# TT_PulseGen_V1_1.net
KiCad netlist of a schematic drawn in EAGLE
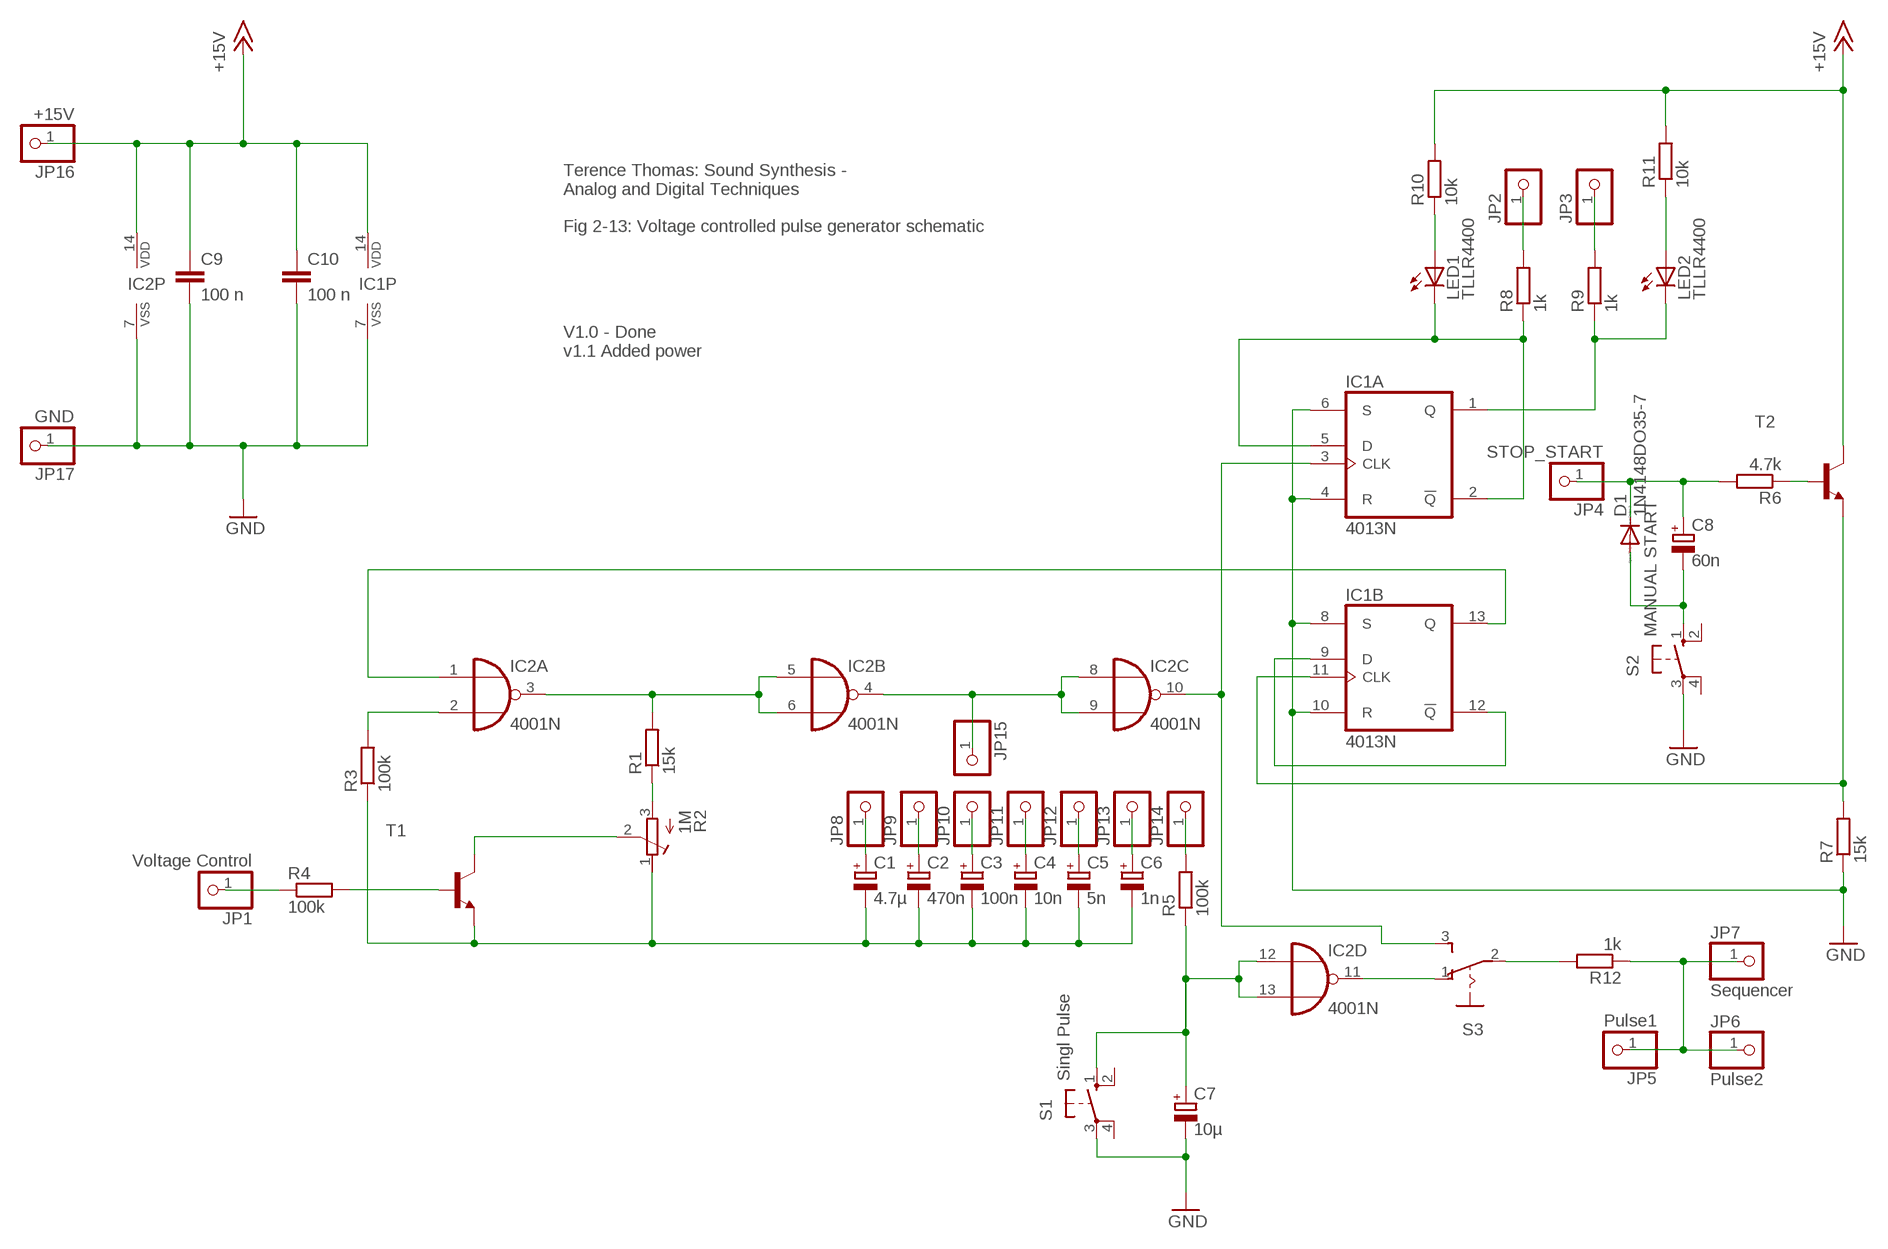
[diagram p0: schematic, sheet 1]

(export (version "E")
  (design (tool "Eeschema 10.0.6"))
  (components
    (comp (ref "C1")
      (value "4.7µ")
      (footprint "eagle-import:E2,5-5")
      (libsource (lib "eagle-import") (part "CPOL-EUE2.5-5"))
    )
    (comp (ref "C2")
      (value "470n")
      (footprint "eagle-import:E2,5-5")
      (libsource (lib "eagle-import") (part "CPOL-EUE2.5-5"))
    )
    (comp (ref "C3")
      (value "100n")
      (footprint "eagle-import:E2,5-5")
      (libsource (lib "eagle-import") (part "CPOL-EUE2.5-5"))
    )
    (comp (ref "C4")
      (value "10n")
      (footprint "eagle-import:E2,5-5")
      (libsource (lib "eagle-import") (part "CPOL-EUE2.5-5"))
    )
    (comp (ref "C5")
      (value "5n")
      (footprint "eagle-import:E2,5-5")
      (libsource (lib "eagle-import") (part "CPOL-EUE2.5-5"))
    )
    (comp (ref "C6")
      (value "1n")
      (footprint "eagle-import:E2,5-5")
      (libsource (lib "eagle-import") (part "CPOL-EUE2.5-5"))
    )
    (comp (ref "C7")
      (value "10µ")
      (footprint "eagle-import:E2,5-5")
      (libsource (lib "eagle-import") (part "CPOL-EUE2.5-5"))
    )
    (comp (ref "C8")
      (value "60n")
      (footprint "eagle-import:E2,5-5")
      (libsource (lib "eagle-import") (part "CPOL-EUE2.5-5"))
    )
    (comp (ref "C9")
      (value "100 n")
      (footprint "eagle-import:C025-030X050")
      (libsource (lib "eagle-import") (part "C-EU025-030X050"))
    )
    (comp (ref "C10")
      (value "100 n")
      (footprint "eagle-import:C025-030X050")
      (libsource (lib "eagle-import") (part "C-EU025-030X050"))
    )
    (comp (ref "D1")
      (value "1N4148DO35-7")
      (footprint "eagle-import:DO35-7")
      (libsource (lib "eagle-import") (part "1N4148DO35-7"))
    )
    (comp (ref "IC1")
      (value "4013N")
      (footprint "eagle-import:DIL14")
      (libsource (lib "eagle-import") (part "4013N"))
    )
    (comp (ref "IC2")
      (value "4001N")
      (footprint "eagle-import:DIL14")
      (libsource (lib "eagle-import") (part "4001N"))
    )
    (comp (ref "JP1")
      (value "Voltage Control")
      (footprint "eagle-import:1X01")
      (libsource (lib "eagle-import") (part "PINHD-1X1"))
    )
    (comp (ref "JP2")
      (value "PINHD-1X1")
      (footprint "eagle-import:1X01")
      (libsource (lib "eagle-import") (part "PINHD-1X1"))
    )
    (comp (ref "JP3")
      (value "PINHD-1X1")
      (footprint "eagle-import:1X01")
      (libsource (lib "eagle-import") (part "PINHD-1X1"))
    )
    (comp (ref "JP4")
      (value "STOP_START")
      (footprint "eagle-import:1X01")
      (libsource (lib "eagle-import") (part "PINHD-1X1"))
    )
    (comp (ref "JP5")
      (value "Pulse1")
      (footprint "eagle-import:1X01")
      (libsource (lib "eagle-import") (part "PINHD-1X1"))
    )
    (comp (ref "JP6")
      (value "Pulse2")
      (footprint "eagle-import:1X01")
      (libsource (lib "eagle-import") (part "PINHD-1X1"))
    )
    (comp (ref "JP7")
      (value "Sequencer")
      (footprint "eagle-import:1X01")
      (libsource (lib "eagle-import") (part "PINHD-1X1"))
    )
    (comp (ref "JP8")
      (value "PINHD-1X1")
      (footprint "eagle-import:1X01")
      (libsource (lib "eagle-import") (part "PINHD-1X1"))
    )
    (comp (ref "JP9")
      (value "PINHD-1X1")
      (footprint "eagle-import:1X01")
      (libsource (lib "eagle-import") (part "PINHD-1X1"))
    )
    (comp (ref "JP10")
      (value "PINHD-1X1")
      (footprint "eagle-import:1X01")
      (libsource (lib "eagle-import") (part "PINHD-1X1"))
    )
    (comp (ref "JP11")
      (value "PINHD-1X1")
      (footprint "eagle-import:1X01")
      (libsource (lib "eagle-import") (part "PINHD-1X1"))
    )
    (comp (ref "JP12")
      (value "PINHD-1X1")
      (footprint "eagle-import:1X01")
      (libsource (lib "eagle-import") (part "PINHD-1X1"))
    )
    (comp (ref "JP13")
      (value "PINHD-1X1")
      (footprint "eagle-import:1X01")
      (libsource (lib "eagle-import") (part "PINHD-1X1"))
    )
    (comp (ref "JP14")
      (value "PINHD-1X1")
      (footprint "eagle-import:1X01")
      (libsource (lib "eagle-import") (part "PINHD-1X1"))
    )
    (comp (ref "JP15")
      (value "PINHD-1X1")
      (footprint "eagle-import:1X01")
      (libsource (lib "eagle-import") (part "PINHD-1X1"))
    )
    (comp (ref "JP16")
      (value "+15V")
      (footprint "eagle-import:1X01")
      (libsource (lib "eagle-import") (part "PINHD-1X1"))
    )
    (comp (ref "JP17")
      (value "GND")
      (footprint "eagle-import:1X01")
      (libsource (lib "eagle-import") (part "PINHD-1X1"))
    )
    (comp (ref "LED1")
      (value "TLLR4400")
      (footprint "eagle-import:LED3MM")
      (fields (field (name "MF") "VISHAY SEMICONDUCTOR"))
      (libsource (lib "eagle-import") (part "TLLR4400"))
    )
    (comp (ref "LED2")
      (value "TLLR4400")
      (footprint "eagle-import:LED3MM")
      (fields (field (name "MF") "VISHAY SEMICONDUCTOR"))
      (libsource (lib "eagle-import") (part "TLLR4400"))
    )
    (comp (ref "R1")
      (value "15k")
      (footprint "eagle-import:0204_7")
      (libsource (lib "eagle-import") (part "R-EU_0204/7"))
    )
    (comp (ref "R2")
      (value "1M")
      (footprint "eagle-import:RTRIMT93YA")
      (libsource (lib "eagle-import") (part "R-TRIMMT93YA"))
    )
    (comp (ref "R3")
      (value "100k")
      (footprint "eagle-import:0204_7")
      (libsource (lib "eagle-import") (part "R-EU_0204/7"))
    )
    (comp (ref "R4")
      (value "100k")
      (footprint "eagle-import:0204_7")
      (libsource (lib "eagle-import") (part "R-EU_0204/7"))
    )
    (comp (ref "R5")
      (value "100k")
      (footprint "eagle-import:0204_7")
      (libsource (lib "eagle-import") (part "R-EU_0204/7"))
    )
    (comp (ref "R6")
      (value "4.7k")
      (footprint "eagle-import:0204_7")
      (libsource (lib "eagle-import") (part "R-EU_0204/7"))
    )
    (comp (ref "R7")
      (value "15k")
      (footprint "eagle-import:0204_7")
      (libsource (lib "eagle-import") (part "R-EU_0204/7"))
    )
    (comp (ref "R8")
      (value "1k")
      (footprint "eagle-import:0204_7")
      (libsource (lib "eagle-import") (part "R-EU_0204/7"))
    )
    (comp (ref "R9")
      (value "1k")
      (footprint "eagle-import:0204_7")
      (libsource (lib "eagle-import") (part "R-EU_0204/7"))
    )
    (comp (ref "R10")
      (value "10k")
      (footprint "eagle-import:0204_7")
      (libsource (lib "eagle-import") (part "R-EU_0204/7"))
    )
    (comp (ref "R11")
      (value "10k")
      (footprint "eagle-import:0204_7")
      (libsource (lib "eagle-import") (part "R-EU_0204/7"))
    )
    (comp (ref "R12")
      (value "1k")
      (footprint "eagle-import:0204_7")
      (libsource (lib "eagle-import") (part "R-EU_0204/7"))
    )
    (comp (ref "S1")
      (value "Singl Pulse")
      (footprint "eagle-import:B3F-10XX")
      (fields (field (name "MPN") "B3F-1000"))
      (libsource (lib "eagle-import") (part "10-XX"))
    )
    (comp (ref "S2")
      (value "MANUAL START")
      (footprint "eagle-import:B3F-10XX")
      (fields (field (name "MPN") "B3F-1000"))
      (libsource (lib "eagle-import") (part "10-XX"))
    )
    (comp (ref "S3")
      (value "M251")
      (footprint "eagle-import:M251")
      (libsource (lib "eagle-import") (part "M251"))
    )
    (comp (ref "T1")
      (value "-NPN-TO92-EBC")
      (footprint "eagle-import:TO92-EBC")
      (libsource (lib "eagle-import") (part "-NPN-TO92-EBC"))
    )
    (comp (ref "T2")
      (value "-NPN-TO92-EBC")
      (footprint "eagle-import:TO92-EBC")
      (libsource (lib "eagle-import") (part "-NPN-TO92-EBC"))
    )
  )
  (nets
    (net (code "1") (name "+15V") (class "Default")
      (node (ref "C10") (pin "1") (pinfunction "1_1") (pintype "passive"))
      (node (ref "C9") (pin "1") (pinfunction "1_1") (pintype "passive"))
      (node (ref "IC1") (pin "14") (pinfunction "VDD_14") (pintype "power_in"))
      (node (ref "IC2") (pin "14") (pinfunction "VDD_14") (pintype "power_in"))
      (node (ref "JP16") (pin "1") (pinfunction "1_1") (pintype "passive"))
      (node (ref "R10") (pin "2") (pinfunction "2_2") (pintype "passive"))
      (node (ref "R11") (pin "2") (pinfunction "2_2") (pintype "passive"))
      (node (ref "T2") (pin "C") (pinfunction "C_C") (pintype "passive"))
    )
    (net (code "2") (name "GND") (class "Default")
      (node (ref "C10") (pin "2") (pinfunction "2_2") (pintype "passive"))
      (node (ref "C7") (pin "-") (pinfunction "-_-") (pintype "passive"))
      (node (ref "C9") (pin "2") (pinfunction "2_2") (pintype "passive"))
      (node (ref "IC1") (pin "10") (pinfunction "R_10") (pintype "input"))
      (node (ref "IC1") (pin "4") (pinfunction "R_4") (pintype "input"))
      (node (ref "IC1") (pin "6") (pinfunction "S_6") (pintype "input"))
      (node (ref "IC1") (pin "7") (pinfunction "VSS_7") (pintype "power_in"))
      (node (ref "IC1") (pin "8") (pinfunction "S_8") (pintype "input"))
      (node (ref "IC2") (pin "7") (pinfunction "VSS_7") (pintype "power_in"))
      (node (ref "JP17") (pin "1") (pinfunction "1_1") (pintype "passive"))
      (node (ref "R7") (pin "1") (pinfunction "1_1") (pintype "passive"))
      (node (ref "S1") (pin "3") (pinfunction "P_3") (pintype "passive"))
      (node (ref "S2") (pin "3") (pinfunction "P_3") (pintype "passive"))
    )
    (net (code "3") (name "Net-(C1-Pad+)") (class "Default")
      (node (ref "C1") (pin "+") (pinfunction "+_+") (pintype "passive"))
      (node (ref "JP8") (pin "1") (pinfunction "1_1") (pintype "passive"))
    )
    (net (code "4") (name "Net-(C2-Pad+)") (class "Default")
      (node (ref "C2") (pin "+") (pinfunction "+_+") (pintype "passive"))
      (node (ref "JP9") (pin "1") (pinfunction "1_1") (pintype "passive"))
    )
    (net (code "5") (name "Net-(C3-Pad+)") (class "Default")
      (node (ref "C3") (pin "+") (pinfunction "+_+") (pintype "passive"))
      (node (ref "JP10") (pin "1") (pinfunction "1_1") (pintype "passive"))
    )
    (net (code "6") (name "Net-(C4-Pad+)") (class "Default")
      (node (ref "C4") (pin "+") (pinfunction "+_+") (pintype "passive"))
      (node (ref "JP11") (pin "1") (pinfunction "1_1") (pintype "passive"))
    )
    (net (code "7") (name "Net-(C5-Pad+)") (class "Default")
      (node (ref "C5") (pin "+") (pinfunction "+_+") (pintype "passive"))
      (node (ref "JP12") (pin "1") (pinfunction "1_1") (pintype "passive"))
    )
    (net (code "8") (name "Net-(C6-Pad+)") (class "Default")
      (node (ref "C6") (pin "+") (pinfunction "+_+") (pintype "passive"))
      (node (ref "JP13") (pin "1") (pinfunction "1_1") (pintype "passive"))
    )
    (net (code "9") (name "Net-(C8-Pad+)") (class "Default")
      (node (ref "C8") (pin "+") (pinfunction "+_+") (pintype "passive"))
      (node (ref "D1") (pin "C") (pinfunction "C_C") (pintype "passive"))
      (node (ref "JP4") (pin "1") (pinfunction "1_1") (pintype "passive"))
      (node (ref "R6") (pin "2") (pinfunction "2_2") (pintype "passive"))
    )
    (net (code "10") (name "Net-(IC1A-CLK)") (class "Default")
      (node (ref "IC1") (pin "3") (pinfunction "CLK_3") (pintype "input"))
      (node (ref "IC2") (pin "10") (pinfunction "O_10") (pintype "output"))
      (node (ref "S3") (pin "3") (pinfunction "S_3") (pintype "passive"))
    )
    (net (code "11") (name "Net-(IC1A-D)") (class "Default")
      (node (ref "IC1") (pin "2") (pinfunction "~{Q}_2") (pintype "output"))
      (node (ref "IC1") (pin "5") (pinfunction "D_5") (pintype "input"))
      (node (ref "LED1") (pin "K") (pinfunction "C_K") (pintype "passive"))
      (node (ref "R8") (pin "1") (pinfunction "1_1") (pintype "passive"))
    )
    (net (code "12") (name "Net-(IC1A-Q)") (class "Default")
      (node (ref "IC1") (pin "1") (pinfunction "Q_1") (pintype "output"))
      (node (ref "LED2") (pin "K") (pinfunction "C_K") (pintype "passive"))
      (node (ref "R9") (pin "1") (pinfunction "1_1") (pintype "passive"))
    )
    (net (code "13") (name "Net-(IC1B-CLK)") (class "Default")
      (node (ref "IC1") (pin "11") (pinfunction "CLK_11") (pintype "input"))
      (node (ref "R7") (pin "2") (pinfunction "2_2") (pintype "passive"))
      (node (ref "T2") (pin "E") (pinfunction "E_E") (pintype "passive"))
    )
    (net (code "14") (name "Net-(IC1B-D)") (class "Default")
      (node (ref "IC1") (pin "12") (pinfunction "~{Q}_12") (pintype "output"))
      (node (ref "IC1") (pin "9") (pinfunction "D_9") (pintype "input"))
    )
    (net (code "15") (name "Net-(IC1B-Q)") (class "Default")
      (node (ref "IC1") (pin "13") (pinfunction "Q_13") (pintype "output"))
      (node (ref "IC2") (pin "1") (pinfunction "I0_1") (pintype "input"))
    )
    (net (code "16") (name "Net-(IC2A-I1)") (class "Default")
      (node (ref "IC2") (pin "2") (pinfunction "I1_2") (pintype "input"))
      (node (ref "R3") (pin "2") (pinfunction "2_2") (pintype "passive"))
    )
    (net (code "17") (name "Net-(IC2A-O)") (class "Default")
      (node (ref "IC2") (pin "3") (pinfunction "O_3") (pintype "output"))
      (node (ref "IC2") (pin "5") (pinfunction "I0_5") (pintype "input"))
      (node (ref "IC2") (pin "6") (pinfunction "I1_6") (pintype "input"))
      (node (ref "R1") (pin "2") (pinfunction "2_2") (pintype "passive"))
    )
    (net (code "18") (name "Net-(IC2B-O)") (class "Default")
      (node (ref "IC2") (pin "4") (pinfunction "O_4") (pintype "output"))
      (node (ref "IC2") (pin "8") (pinfunction "I0_8") (pintype "input"))
      (node (ref "IC2") (pin "9") (pinfunction "I1_9") (pintype "input"))
      (node (ref "JP15") (pin "1") (pinfunction "1_1") (pintype "passive"))
    )
    (net (code "19") (name "Net-(IC2D-I0)") (class "Default")
      (node (ref "C7") (pin "+") (pinfunction "+_+") (pintype "passive"))
      (node (ref "IC2") (pin "12") (pinfunction "I0_12") (pintype "input"))
      (node (ref "IC2") (pin "13") (pinfunction "I1_13") (pintype "input"))
      (node (ref "R5") (pin "1") (pinfunction "1_1") (pintype "passive"))
      (node (ref "S1") (pin "1") (pinfunction "S_1") (pintype "passive"))
    )
    (net (code "20") (name "Net-(IC2D-O)") (class "Default")
      (node (ref "IC2") (pin "11") (pinfunction "O_11") (pintype "output"))
      (node (ref "S3") (pin "1") (pinfunction "O_1") (pintype "passive"))
    )
    (net (code "21") (name "Net-(JP1-Pad1)") (class "Default")
      (node (ref "JP1") (pin "1") (pinfunction "1_1") (pintype "passive"))
      (node (ref "R4") (pin "1") (pinfunction "1_1") (pintype "passive"))
    )
    (net (code "22") (name "Net-(JP2-Pad1)") (class "Default")
      (node (ref "JP2") (pin "1") (pinfunction "1_1") (pintype "passive"))
      (node (ref "R8") (pin "2") (pinfunction "2_2") (pintype "passive"))
    )
    (net (code "23") (name "Net-(JP3-Pad1)") (class "Default")
      (node (ref "JP3") (pin "1") (pinfunction "1_1") (pintype "passive"))
      (node (ref "R9") (pin "2") (pinfunction "2_2") (pintype "passive"))
    )
    (net (code "24") (name "Net-(JP5-Pad1)") (class "Default")
      (node (ref "JP5") (pin "1") (pinfunction "1_1") (pintype "passive"))
      (node (ref "JP6") (pin "1") (pinfunction "1_1") (pintype "passive"))
      (node (ref "JP7") (pin "1") (pinfunction "1_1") (pintype "passive"))
      (node (ref "R12") (pin "1") (pinfunction "1_1") (pintype "passive"))
    )
    (net (code "25") (name "Net-(JP14-Pad1)") (class "Default")
      (node (ref "JP14") (pin "1") (pinfunction "1_1") (pintype "passive"))
      (node (ref "R5") (pin "2") (pinfunction "2_2") (pintype "passive"))
    )
    (net (code "26") (name "Net-(LED1-PadA)") (class "Default")
      (node (ref "LED1") (pin "A") (pinfunction "A_A") (pintype "passive"))
      (node (ref "R10") (pin "1") (pinfunction "1_1") (pintype "passive"))
    )
    (net (code "27") (name "Net-(LED2-PadA)") (class "Default")
      (node (ref "LED2") (pin "A") (pinfunction "A_A") (pintype "passive"))
      (node (ref "R11") (pin "1") (pinfunction "1_1") (pintype "passive"))
    )
    (net (code "28") (name "Net-(R2-A)") (class "Default")
      (node (ref "R1") (pin "1") (pinfunction "1_1") (pintype "passive"))
      (node (ref "R2") (pin "3") (pinfunction "A_3") (pintype "passive"))
    )
    (net (code "29") (name "Net-(R2-E)") (class "Default")
      (node (ref "C1") (pin "-") (pinfunction "-_-") (pintype "passive"))
      (node (ref "C2") (pin "-") (pinfunction "-_-") (pintype "passive"))
      (node (ref "C3") (pin "-") (pinfunction "-_-") (pintype "passive"))
      (node (ref "C4") (pin "-") (pinfunction "-_-") (pintype "passive"))
      (node (ref "C5") (pin "-") (pinfunction "-_-") (pintype "passive"))
      (node (ref "C6") (pin "-") (pinfunction "-_-") (pintype "passive"))
      (node (ref "R2") (pin "1") (pinfunction "E_1") (pintype "passive"))
      (node (ref "R3") (pin "1") (pinfunction "1_1") (pintype "passive"))
      (node (ref "T1") (pin "E") (pinfunction "E_E") (pintype "passive"))
    )
    (net (code "30") (name "Net-(R2-S)") (class "Default")
      (node (ref "R2") (pin "2") (pinfunction "S_2") (pintype "passive"))
      (node (ref "T1") (pin "C") (pinfunction "C_C") (pintype "passive"))
    )
    (net (code "31") (name "Net-(R4-Pad2)") (class "Default")
      (node (ref "R4") (pin "2") (pinfunction "2_2") (pintype "passive"))
      (node (ref "T1") (pin "B") (pinfunction "B_B") (pintype "passive"))
    )
    (net (code "32") (name "Net-(R6-Pad1)") (class "Default")
      (node (ref "R6") (pin "1") (pinfunction "1_1") (pintype "passive"))
      (node (ref "T2") (pin "B") (pinfunction "B_B") (pintype "passive"))
    )
    (net (code "33") (name "Net-(S2-S)") (class "Default")
      (node (ref "C8") (pin "-") (pinfunction "-_-") (pintype "passive"))
      (node (ref "D1") (pin "A") (pinfunction "A_A") (pintype "passive"))
      (node (ref "S2") (pin "1") (pinfunction "S_1") (pintype "passive"))
    )
    (net (code "34") (name "Net-(S3-P)") (class "Default")
      (node (ref "R12") (pin "2") (pinfunction "2_2") (pintype "passive"))
      (node (ref "S3") (pin "2") (pinfunction "P_2") (pintype "passive"))
    )
    (net (code "35") (name "unconnected-(S1-P1-Pad4)") (class "Default")
      (node (ref "S1") (pin "4") (pinfunction "P1_4") (pintype "passive"))
    )
    (net (code "36") (name "unconnected-(S1-S1-Pad2)") (class "Default")
      (node (ref "S1") (pin "2") (pinfunction "S1_2") (pintype "passive"))
    )
    (net (code "37") (name "unconnected-(S2-P1-Pad4)") (class "Default")
      (node (ref "S2") (pin "4") (pinfunction "P1_4") (pintype "passive"))
    )
    (net (code "38") (name "unconnected-(S2-S1-Pad2)") (class "Default")
      (node (ref "S2") (pin "2") (pinfunction "S1_2") (pintype "passive"))
    )
  )
)
